# LightDimmer.net
KiCad netlist of a schematic drawn in Altium Designer
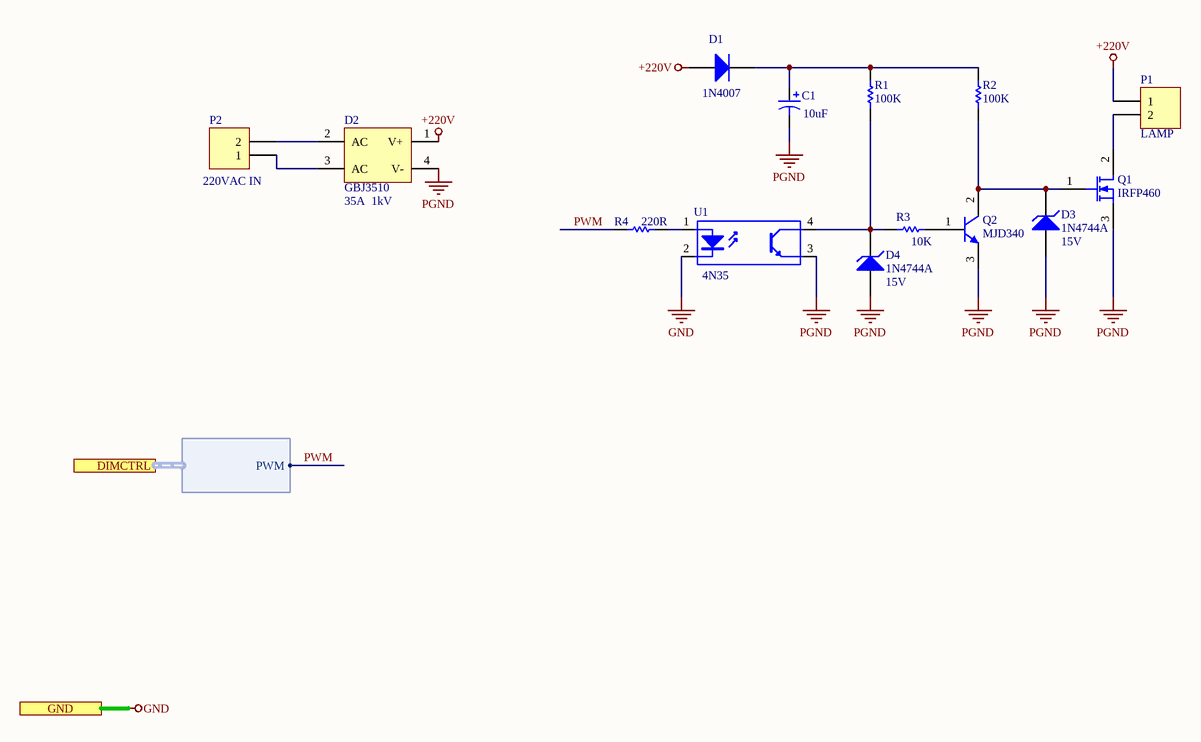
[diagram p0: LightDimmer.SchDoc]

(export (version "E")
  (design (tool "Eeschema 10.0.6"))
  (components
    (comp (ref "C1")
      (value "10uF")
      (footprint "RB7.6-15")
      (description "Polarized Capacitor (Radial)")
      (fields (field (name "Comment") "10uF/400V") (field (name "PUBLISHER") "Altium Limited"))
      (libsource (lib "Miscellaneous Devices") (part "Cap Pol1"))
    )
    (comp (ref "D1")
      (value "1N4007")
      (footprint "D-SOD-80")
      (description "1 Amp General Purpose Rectifier (M7)")
      (libsource (lib "Miscellaneous Devices") (part "Diode 1N4004"))
    )
    (comp (ref "D2")
      (value "GBJ3510")
      (footprint "D-46_6A")
      (description "35A/1000V")
      (fields
        (field (name "MANUFACTURER") "MCC")
        (field (name "MANUFACTURER PART NUMBER") "GBJ3510-BP")
        (field (name "FORWARD CURRENT") "35A")
        (field (name "MAX REPETITIVE REVERSE VOLTAGE (VRRM)") "1kV")
      )
      (libsource (lib "Miscellaneous Devices") (part "Bridge2"))
    )
    (comp (ref "D3")
      (value "1N4744A")
      (footprint "DIODE-0.7")
      (description "1W 15V")
      (fields
        (field (name "MANUFACTURER") "MCC")
        (field (name "MANUFACTURER PART NUMBER") "1N4744A-TP")
        (field (name "ZENER VOLTAGE") "15V")
      )
      (libsource (lib "Miscellaneous Devices") (part "D Zener"))
    )
    (comp (ref "D4")
      (value "1N4744A")
      (footprint "DIODE-0.7")
      (description "1W 15V")
      (fields
        (field (name "MANUFACTURER") "MCC")
        (field (name "MANUFACTURER PART NUMBER") "1N4744A-TP")
        (field (name "ZENER VOLTAGE") "15V")
      )
      (libsource (lib "Miscellaneous Devices") (part "D Zener"))
    )
    (comp (ref "P1")
      (value "LAMP")
      (footprint "HDR1X2")
      (description "Header, 2-Pin")
      (fields (field (name "Comment") "KF128-2P"))
      (libsource (lib "") (part "Header 2_1"))
    )
    (comp (ref "P2")
      (value "220VAC IN")
      (footprint "HDR1X2")
      (description "Header, 2-Pin")
      (fields (field (name "Comment") "KF128-2P"))
      (libsource (lib "Miscellaneous Connectors") (part "Header 2"))
    )
    (comp (ref "Q1")
      (value "IRFP460")
      (footprint "TO-247-3B")
      (description "N-Channel MOSFET 500V/20A")
      (fields (field (name "MANUFACTURER") "Vishay") (field (name "MANUFACTURER PART NUMBER") "IRFP460PBF"))
      (libsource (lib "Miscellaneous Devices") (part "MOSFET-N"))
    )
    (comp (ref "Q2")
      (value "MJD340")
      (footprint "TO-252-3")
      (description "NPN Bipolar Transistor")
      (fields
        (field (name "MANUFACTURER") "ON Semiconductor")
        (field (name "MANUFACTURER PART NUMBER") "MJD340T4G")
      )
      (libsource (lib "Miscellaneous Devices") (part "NPN"))
    )
    (comp (ref "R1")
      (value "100K")
      (footprint "AXIAL-0.3")
      (description "Resistor")
      (libsource (lib "Miscellaneous Devices") (part "Res1"))
    )
    (comp (ref "R2")
      (value "100K")
      (footprint "AXIAL-0.3")
      (description "Resistor")
      (libsource (lib "Miscellaneous Devices") (part "Res1"))
    )
    (comp (ref "R3")
      (value "10K")
      (footprint "AXIAL-0.3")
      (description "Resistor")
      (libsource (lib "Miscellaneous Devices") (part "Res1"))
    )
    (comp (ref "R4")
      (value "220R")
      (footprint "AXIAL-0.3")
      (description "Resistor")
      (libsource (lib "Miscellaneous Devices") (part "Res1"))
    )
    (comp (ref "U1")
      (value "4N35")
      (footprint "DIP-4")
      (description "4-Pin Phototransistor Optocoupler")
      (fields (field (name "MANUFACTURER") "Vishay"))
      (libsource (lib "Miscellaneous Devices") (part "Optoisolator1"))
    )
  )
  (nets
    (net (code "2") (name "+220V") (class "Default")
      (node (ref "D1") (pin "1") (pinfunction "A_1") (pintype "passive"))
      (node (ref "D2") (pin "1") (pinfunction "V+_1") (pintype "passive"))
      (node (ref "P1") (pin "1") (pinfunction "1_1") (pintype "passive"))
    )
    (net (code "3") (name "/PWM") (class "Default")
      (node (ref "R4") (pin "2") (pinfunction "2_2") (pintype "passive"))
    )
    (net (code "5") (name "GND") (class "Default")
      (node (ref "U1") (pin "2") (pinfunction "K_2") (pintype "passive"))
    )
    (net (code "6") (name "Net-(D1-K)") (class "Default")
      (node (ref "C1") (pin "1") (pinfunction "1_1") (pintype "passive"))
      (node (ref "D1") (pin "2") (pinfunction "K_2") (pintype "passive"))
      (node (ref "R1") (pin "1") (pinfunction "1_1") (pintype "passive"))
      (node (ref "R2") (pin "1") (pinfunction "1_1") (pintype "passive"))
    )
    (net (code "7") (name "Net-(D2-AC-Pad2)") (class "Default")
      (node (ref "D2") (pin "2") (pinfunction "AC_2") (pintype "passive"))
      (node (ref "P2") (pin "2") (pinfunction "2_2") (pintype "passive"))
    )
    (net (code "8") (name "Net-(D2-AC-Pad3)") (class "Default")
      (node (ref "D2") (pin "3") (pinfunction "AC_3") (pintype "passive"))
      (node (ref "P2") (pin "1") (pinfunction "1_1") (pintype "passive"))
    )
    (net (code "9") (name "Net-(D3-K)") (class "Default")
      (node (ref "D3") (pin "2") (pinfunction "K_2") (pintype "passive"))
      (node (ref "Q1") (pin "1") (pinfunction "G_1") (pintype "passive"))
      (node (ref "Q2") (pin "2") (pinfunction "C_2") (pintype "passive"))
      (node (ref "R2") (pin "2") (pinfunction "2_2") (pintype "passive"))
    )
    (net (code "10") (name "Net-(D4-K)") (class "Default")
      (node (ref "D4") (pin "2") (pinfunction "K_2") (pintype "passive"))
      (node (ref "R1") (pin "2") (pinfunction "2_2") (pintype "passive"))
      (node (ref "R3") (pin "2") (pinfunction "2_2") (pintype "passive"))
      (node (ref "U1") (pin "4") (pinfunction "C_4") (pintype "passive"))
    )
    (net (code "11") (name "Net-(Q1-D)") (class "Default")
      (node (ref "P1") (pin "2") (pinfunction "2_2") (pintype "passive"))
      (node (ref "Q1") (pin "2") (pinfunction "D_2") (pintype "passive"))
    )
    (net (code "12") (name "Net-(Q2-B)") (class "Default")
      (node (ref "Q2") (pin "1") (pinfunction "B_1") (pintype "passive"))
      (node (ref "R3") (pin "1") (pinfunction "1_1") (pintype "passive"))
    )
    (net (code "13") (name "Net-(U1-A)") (class "Default")
      (node (ref "R4") (pin "1") (pinfunction "1_1") (pintype "passive"))
      (node (ref "U1") (pin "1") (pinfunction "A_1") (pintype "passive"))
    )
    (net (code "14") (name "PGND") (class "Default")
      (node (ref "C1") (pin "2") (pinfunction "2_2") (pintype "passive"))
      (node (ref "D2") (pin "4") (pinfunction "V-_4") (pintype "passive"))
      (node (ref "D3") (pin "1") (pinfunction "A_1") (pintype "passive"))
      (node (ref "D4") (pin "1") (pinfunction "A_1") (pintype "passive"))
      (node (ref "Q1") (pin "3") (pinfunction "S_3") (pintype "passive"))
      (node (ref "Q2") (pin "3") (pinfunction "E_3") (pintype "passive"))
      (node (ref "U1") (pin "3") (pinfunction "E_3") (pintype "passive"))
    )
  )
)
